# punto5sq.net
KiCad netlist of a schematic drawn in Altium Designer
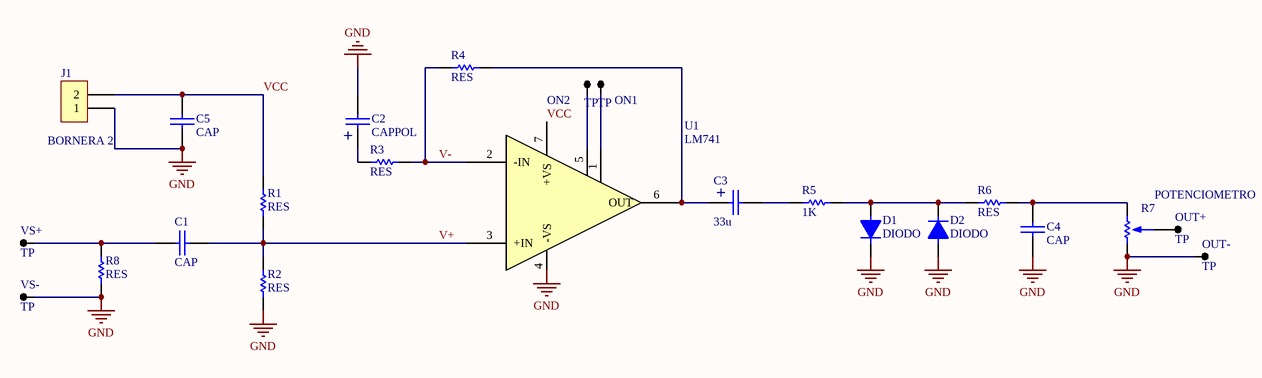
[diagram p0: punto5sq.SchDoc]

(export (version "E")
  (design (tool "Eeschema 10.0.6"))
  (components
    (comp (ref "C1") (value "CAP") (footprint "CAP200") (libsource (lib "LIBEBAL") (part "CAP")))
    (comp (ref "C2") (value "CAPPOL") (footprint "CAP100RP") (libsource (lib "LIBEBAL") (part "CAPPOL")))
    (comp (ref "C3") (value "33u") (footprint "CAP100RP") (libsource (lib "LIBEBAL") (part "CAPPOL")))
    (comp (ref "C4") (value "CAP") (footprint "CAP200") (libsource (lib "LIBEBAL") (part "CAP")))
    (comp (ref "C5") (value "CAP") (footprint "CAP200") (libsource (lib "LIBEBAL") (part "CAP")))
    (comp (ref "D1") (value "DIODO") (footprint "DO41") (libsource (lib "LIBEBAL") (part "DIODO")))
    (comp (ref "D2") (value "DIODO") (footprint "DO41") (libsource (lib "LIBEBAL") (part "DIODO")))
    (comp (ref "J1")
      (value "BORNERA 2")
      (footprint "BORNERA2")
      (libsource (lib "LIBEBAL") (part "BORNERA 2"))
    )
    (comp (ref "ON1") (value "TP") (footprint "TPTH") (libsource (lib "LIBEBAL") (part "TP")))
    (comp (ref "ON2") (value "TP") (footprint "TPTH") (libsource (lib "LIBEBAL") (part "TP")))
    (comp (ref "OUT+") (value "TP") (footprint "TPTH") (libsource (lib "LIBEBAL") (part "TP")))
    (comp (ref "OUT-") (value "TP") (footprint "TPTH") (libsource (lib "LIBEBAL") (part "TP")))
    (comp (ref "R1") (value "RES") (footprint "RES400") (libsource (lib "LIBEBAL") (part "RES")))
    (comp (ref "R2") (value "RES") (footprint "RES400") (libsource (lib "LIBEBAL") (part "RES")))
    (comp (ref "R3") (value "RES") (footprint "RES400") (libsource (lib "LIBEBAL") (part "RES")))
    (comp (ref "R4") (value "RES") (footprint "RES400") (libsource (lib "LIBEBAL") (part "RES")))
    (comp (ref "R5") (value "1K") (footprint "RES400") (libsource (lib "LIBEBAL") (part "RES")))
    (comp (ref "R6") (value "RES") (footprint "RES400") (libsource (lib "LIBEBAL") (part "RES")))
    (comp (ref "R7")
      (value "POTENCIOMETRO")
      (footprint "POTENCIOMETRO")
      (libsource (lib "LIBEBAL") (part "POTENCIOMETRO"))
    )
    (comp (ref "R8") (value "RES") (footprint "RES400") (libsource (lib "LIBEBAL") (part "RES")))
    (comp (ref "U1")
      (value "LM741")
      (footprint "DIP8")
      (description "LM741 Operational Amplifier")
      (libsource (lib "LIBEBAL") (part "LM741"))
    )
    (comp (ref "VS+") (value "TP") (footprint "TPTH") (libsource (lib "LIBEBAL") (part "TP")))
    (comp (ref "VS-") (value "TP") (footprint "TPTH") (libsource (lib "LIBEBAL") (part "TP")))
  )
  (nets
    (net (code "1") (name "/V+") (class "Default")
      (node (ref "C1") (pin "1") (pinfunction "1_1") (pintype "passive"))
      (node (ref "R1") (pin "1") (pinfunction "1_1") (pintype "passive"))
      (node (ref "R2") (pin "2") (pinfunction "2_2") (pintype "passive"))
      (node (ref "U1") (pin "3") (pinfunction "+IN_3") (pintype "passive"))
    )
    (net (code "2") (name "/V-") (class "Default")
      (node (ref "R3") (pin "2") (pinfunction "2_2") (pintype "passive"))
      (node (ref "R4") (pin "1") (pinfunction "1_1") (pintype "passive"))
      (node (ref "U1") (pin "2") (pinfunction "-IN_2") (pintype "passive"))
    )
    (net (code "3") (name "/VCC") (class "Default")
      (node (ref "C5") (pin "1") (pinfunction "1_1") (pintype "passive"))
      (node (ref "J1") (pin "2") (pinfunction "2_2") (pintype "passive"))
      (node (ref "R1") (pin "2") (pinfunction "2_2") (pintype "passive"))
      (node (ref "U1") (pin "7") (pinfunction "+VS_7") (pintype "passive"))
    )
    (net (code "4") (name "GND") (class "Default")
      (node (ref "C2") (pin "2") (pinfunction "2_2") (pintype "passive"))
      (node (ref "C4") (pin "2") (pinfunction "2_2") (pintype "passive"))
      (node (ref "C5") (pin "2") (pinfunction "2_2") (pintype "passive"))
      (node (ref "D1") (pin "2") (pinfunction "2_2") (pintype "passive"))
      (node (ref "D2") (pin "1") (pinfunction "1_1") (pintype "passive"))
      (node (ref "J1") (pin "1") (pinfunction "1_1") (pintype "passive"))
      (node (ref "OUT-") (pin "1") (pinfunction "1_1") (pintype "passive"))
      (node (ref "R2") (pin "1") (pinfunction "1_1") (pintype "passive"))
      (node (ref "R7") (pin "3") (pinfunction "3_3") (pintype "passive"))
      (node (ref "R8") (pin "2") (pinfunction "2_2") (pintype "passive"))
      (node (ref "U1") (pin "4") (pinfunction "-VS_4") (pintype "passive"))
      (node (ref "VS-") (pin "1") (pinfunction "1_1") (pintype "passive"))
    )
    (net (code "5") (name "Net-(C1-Pad2)") (class "Default")
      (node (ref "C1") (pin "2") (pinfunction "2_2") (pintype "passive"))
      (node (ref "R8") (pin "1") (pinfunction "1_1") (pintype "passive"))
      (node (ref "VS+") (pin "1") (pinfunction "1_1") (pintype "passive"))
    )
    (net (code "6") (name "Net-(C2-Pad1)") (class "Default")
      (node (ref "C2") (pin "1") (pinfunction "1_1") (pintype "passive"))
      (node (ref "R3") (pin "1") (pinfunction "1_1") (pintype "passive"))
    )
    (net (code "7") (name "Net-(C3-Pad2)") (class "Default")
      (node (ref "C3") (pin "2") (pinfunction "2_2") (pintype "passive"))
      (node (ref "R5") (pin "1") (pinfunction "1_1") (pintype "passive"))
    )
    (net (code "8") (name "Net-(C4-Pad1)") (class "Default")
      (node (ref "C4") (pin "1") (pinfunction "1_1") (pintype "passive"))
      (node (ref "R6") (pin "2") (pinfunction "2_2") (pintype "passive"))
      (node (ref "R7") (pin "1") (pinfunction "1_1") (pintype "passive"))
    )
    (net (code "9") (name "Net-(D1-Pad1)") (class "Default")
      (node (ref "D1") (pin "1") (pinfunction "1_1") (pintype "passive"))
      (node (ref "D2") (pin "2") (pinfunction "2_2") (pintype "passive"))
      (node (ref "R5") (pin "2") (pinfunction "2_2") (pintype "passive"))
      (node (ref "R6") (pin "1") (pinfunction "1_1") (pintype "passive"))
    )
    (net (code "10") (name "Net-(OUT+-Pad1)") (class "Default")
      (node (ref "OUT+") (pin "1") (pinfunction "1_1") (pintype "passive"))
      (node (ref "R7") (pin "2") (pinfunction "2_2") (pintype "passive"))
    )
    (net (code "11") (name "Net-(U1-+RG)") (class "Default")
      (node (ref "ON2") (pin "1") (pinfunction "1_1") (pintype "passive"))
      (node (ref "U1") (pin "5") (pinfunction "+RG_5") (pintype "passive"))
    )
    (net (code "12") (name "Net-(U1--RG)") (class "Default")
      (node (ref "ON1") (pin "1") (pinfunction "1_1") (pintype "passive"))
      (node (ref "U1") (pin "1") (pinfunction "-RG_1") (pintype "passive"))
    )
    (net (code "13") (name "Net-(U1-OUT)") (class "Default")
      (node (ref "C3") (pin "1") (pinfunction "1_1") (pintype "passive"))
      (node (ref "R4") (pin "2") (pinfunction "2_2") (pintype "passive"))
      (node (ref "U1") (pin "6") (pinfunction "OUT_6") (pintype "passive"))
    )
  )
)
